# BT136-Simple-Soldering-Iron.net
KiCad netlist of a schematic drawn in EAGLE
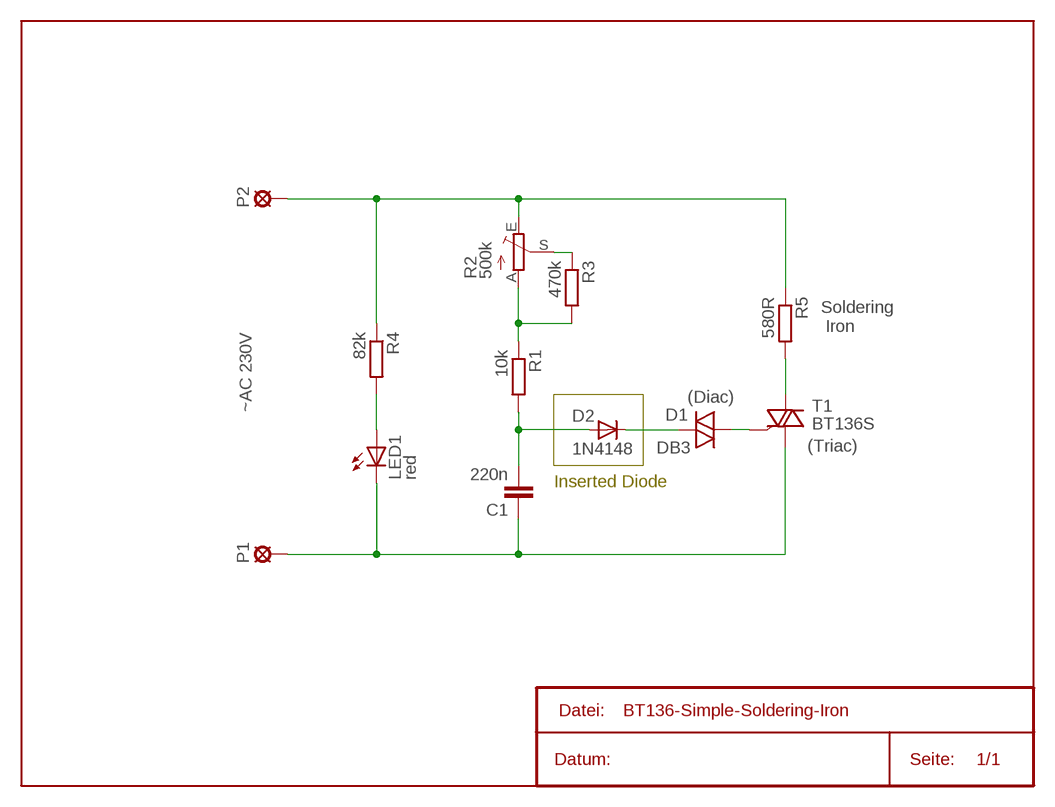
[diagram p0: schematic, sheet 1]

(export (version "E")
  (design (tool "Eeschema 10.0.6"))
  (components
    (comp (ref "C1")
      (value "220n")
      (footprint "eagle-import:C050-025X075")
      (libsource (lib "eagle-import") (part "C-EU050-025X075"))
    )
    (comp (ref "D1")
      (value "DB3")
      (footprint "eagle-import:ER900")
      (libsource (lib "eagle-import") (part "ER900"))
    )
    (comp (ref "D2")
      (value "1N4148")
      (footprint "eagle-import:DO35-7")
      (libsource (lib "eagle-import") (part "1N4148DO35-7"))
    )
    (comp (ref "LED1")
      (value "red")
      (footprint "eagle-import:SML1206")
      (libsource (lib "eagle-import") (part "LEDSML1206"))
    )
    (comp (ref "P1")
      (value "LSP10")
      (footprint "eagle-import:LSP10")
      (libsource (lib "eagle-import") (part "LSP10"))
    )
    (comp (ref "P2")
      (value "LSP10")
      (footprint "eagle-import:LSP10")
      (libsource (lib "eagle-import") (part "LSP10"))
    )
    (comp (ref "R1")
      (value "10k")
      (footprint "eagle-import:R1210")
      (libsource (lib "eagle-import") (part "R-EU_R1210"))
    )
    (comp (ref "R2")
      (value "500k")
      (footprint "eagle-import:RS3")
      (libsource (lib "eagle-import") (part "TRIM_EU-RS3"))
    )
    (comp (ref "R3")
      (value "470k")
      (footprint "eagle-import:R1210")
      (libsource (lib "eagle-import") (part "R-EU_R1210"))
    )
    (comp (ref "R4")
      (value "82k")
      (footprint "eagle-import:R1210")
      (libsource (lib "eagle-import") (part "R-EU_R1210"))
    )
    (comp (ref "R5")
      (value "580R")
      (footprint "eagle-import:0207_7")
      (libsource (lib "eagle-import") (part "R-EU_0207/7"))
    )
    (comp (ref "T1")
      (value "BT136S")
      (footprint "eagle-import:DPAK")
      (libsource (lib "eagle-import") (part "BT136D"))
    )
  )
  (nets
    (net (code "1") (name "Net-(C1-Pad2)") (class "Default")
      (node (ref "C1") (pin "2") (pinfunction "2_2") (pintype "passive"))
      (node (ref "D2") (pin "A") (pinfunction "A_A") (pintype "passive"))
      (node (ref "R1") (pin "2") (pinfunction "2_2") (pintype "passive"))
    )
    (net (code "2") (name "Net-(D1-Pad2)") (class "Default")
      (node (ref "D1") (pin "2") (pinfunction "2_2") (pintype "passive"))
      (node (ref "D2") (pin "C") (pinfunction "C_C") (pintype "passive"))
    )
    (net (code "3") (name "Net-(LED1-PadA)") (class "Default")
      (node (ref "LED1") (pin "A") (pinfunction "A_A") (pintype "passive"))
      (node (ref "R4") (pin "2") (pinfunction "2_2") (pintype "passive"))
    )
    (net (code "4") (name "Net-(P2-PadMP)") (class "Default")
      (node (ref "P2") (pin "MP") (pinfunction "MP_MP") (pintype "passive"))
      (node (ref "R2") (pin "E") (pinfunction "E_E") (pintype "passive"))
      (node (ref "R4") (pin "1") (pinfunction "1_1") (pintype "passive"))
      (node (ref "R5") (pin "1") (pinfunction "1_1") (pintype "passive"))
    )
    (net (code "5") (name "Net-(R1-Pad1)") (class "Default")
      (node (ref "R1") (pin "1") (pinfunction "1_1") (pintype "passive"))
      (node (ref "R2") (pin "A") (pinfunction "A_A") (pintype "passive"))
      (node (ref "R3") (pin "2") (pinfunction "2_2") (pintype "passive"))
    )
    (net (code "6") (name "Net-(R2-PadS)") (class "Default")
      (node (ref "R2") (pin "S") (pinfunction "S_S") (pintype "passive"))
      (node (ref "R3") (pin "1") (pinfunction "1_1") (pintype "passive"))
    )
    (net (code "7") (name "Net-(T1-A1)") (class "Default")
      (node (ref "C1") (pin "1") (pinfunction "1_1") (pintype "passive"))
      (node (ref "LED1") (pin "C") (pinfunction "C_C") (pintype "passive"))
      (node (ref "P1") (pin "MP") (pinfunction "MP_MP") (pintype "passive"))
      (node (ref "T1") (pin "1") (pinfunction "A1_1") (pintype "passive"))
    )
    (net (code "8") (name "Net-(T1-A2)") (class "Default")
      (node (ref "R5") (pin "2") (pinfunction "2_2") (pintype "passive"))
      (node (ref "T1") (pin "4") (pinfunction "A2_4") (pintype "passive"))
    )
    (net (code "9") (name "Net-(T1-G)") (class "Default")
      (node (ref "D1") (pin "1") (pinfunction "1_1") (pintype "passive"))
      (node (ref "T1") (pin "3") (pinfunction "G_3") (pintype "passive"))
    )
  )
)
